# GW-RS485-V40-009.net
KiCad netlist of a schematic drawn in EAGLE
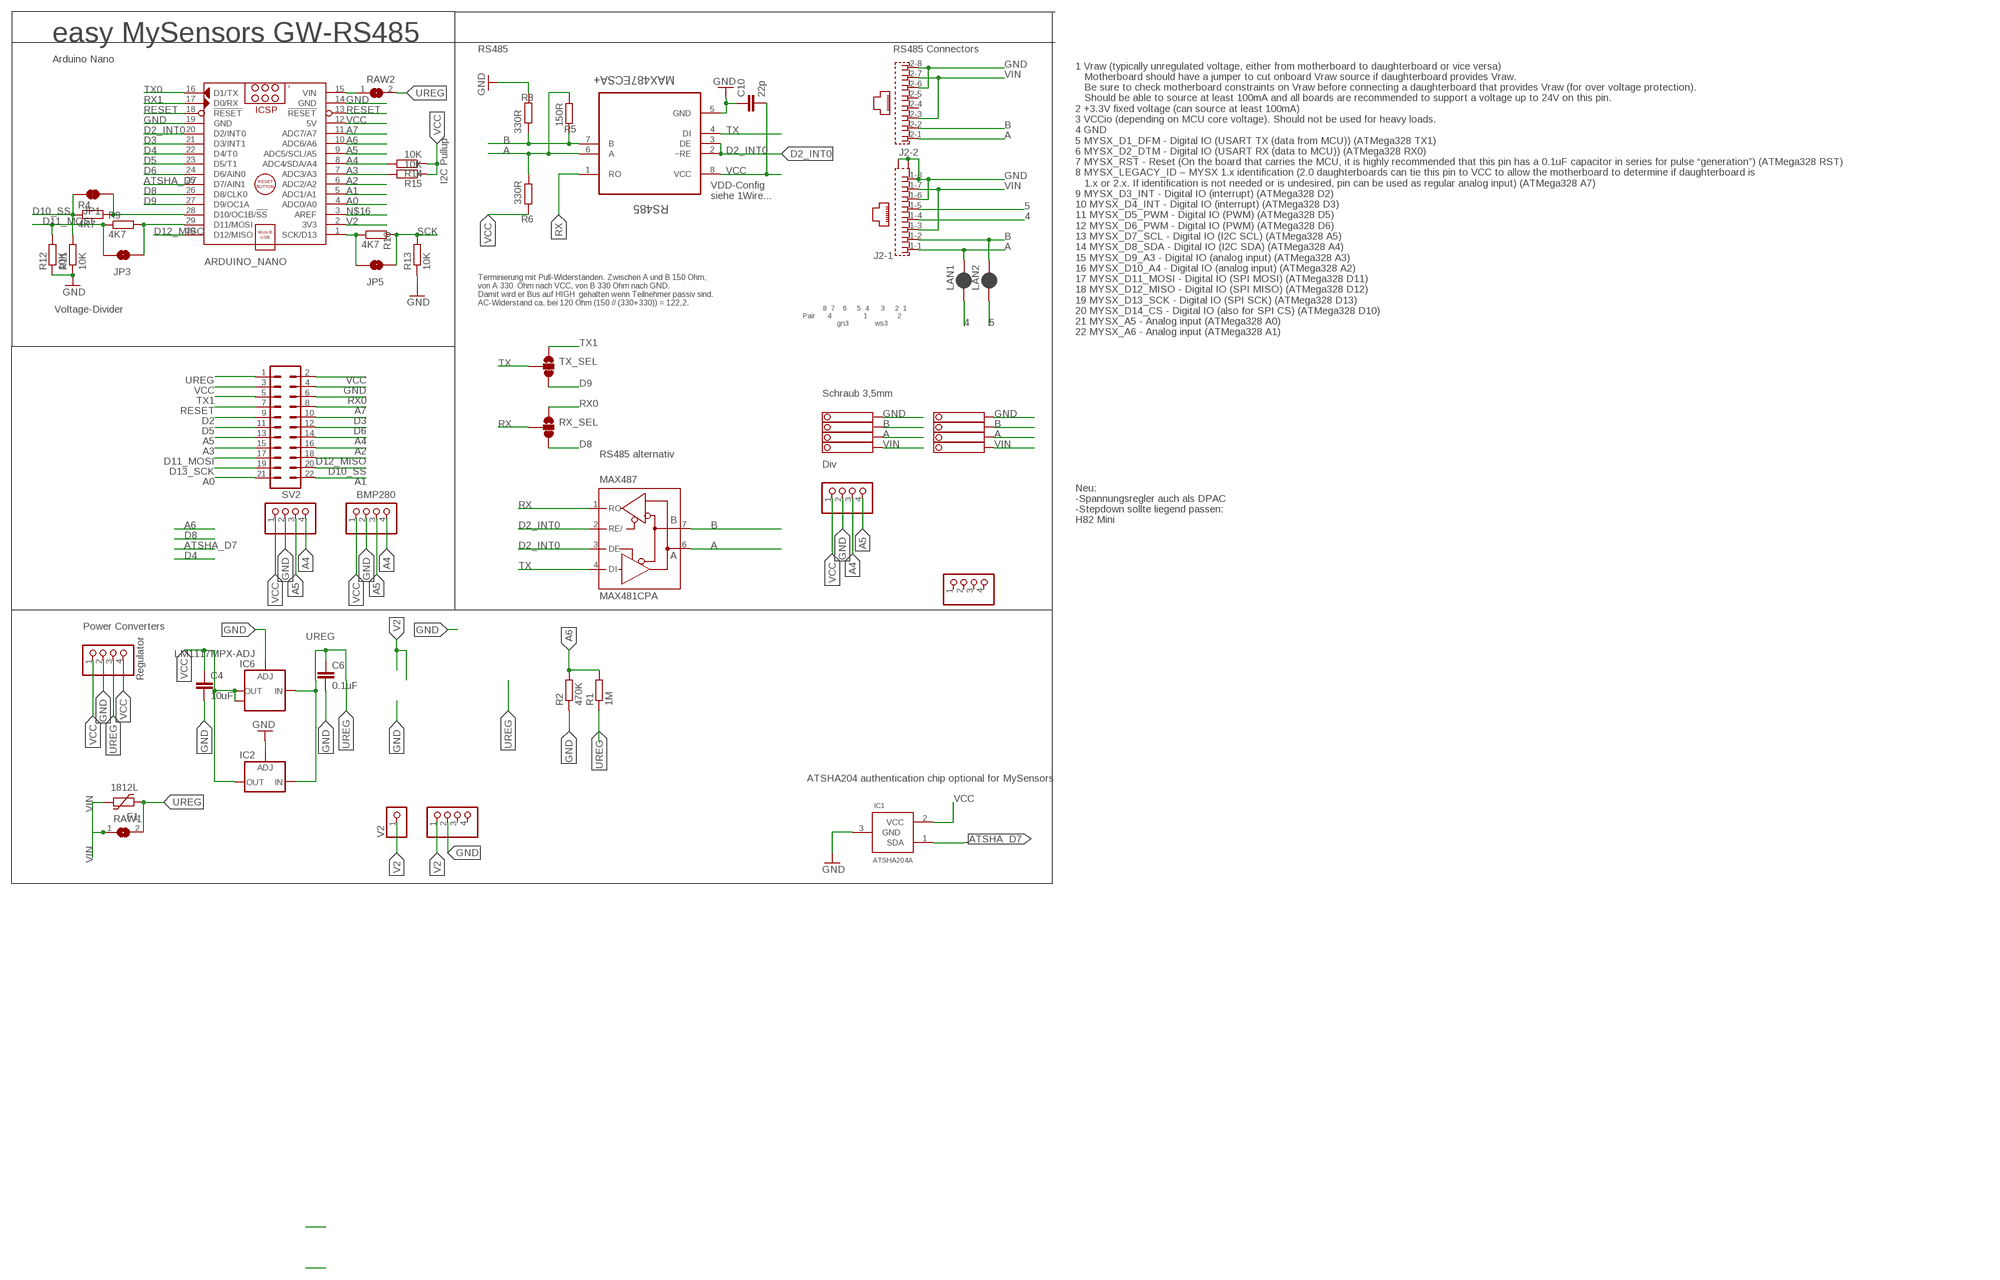
[diagram p0: schematic, sheet 1]

(export (version "E")
  (design (tool "Eeschema 10.0.6"))
  (components
    (comp (ref "ARDUINO_NANO")
      (value "ARDUINO_NANO_OHNE-BOHR")
      (footprint "eagle-import:ARDUINO_NANO")
      (libsource (lib "eagle-import") (part "ARDUINO_NANO_OHNE-BOHR"))
    )
    (comp (ref "BH1750")
      (value "PINHD-1X04_2.54-S")
      (footprint "eagle-import:1X04-S")
      (libsource (lib "eagle-import") (part "PINHD-1X04_2.54-S"))
    )
    (comp (ref "C4")
      (value "10uF")
      (footprint "eagle-import:C1210")
      (libsource (lib "eagle-import") (part "C-EUC1210"))
    )
    (comp (ref "C6")
      (value "0.1uF")
      (footprint "eagle-import:C1206")
      (libsource (lib "eagle-import") (part "C-EUC1206"))
    )
    (comp (ref "C10")
      (value "22p")
      (footprint "eagle-import:C0805")
      (libsource (lib "eagle-import") (part "C-EUC0805"))
    )
    (comp (ref "F1")
      (value "1812L")
      (footprint "eagle-import:1812L")
      (libsource (lib "eagle-import") (part "1812L"))
    )
    (comp (ref "I2C-1")
      (value "PINHD-1X04_2.54-S")
      (footprint "eagle-import:1X04-S")
      (libsource (lib "eagle-import") (part "PINHD-1X04_2.54-S"))
    )
    (comp (ref "I2C-2")
      (value "PINHD-1X04_2.54-S")
      (footprint "eagle-import:1X04-S")
      (libsource (lib "eagle-import") (part "PINHD-1X04_2.54-S"))
    )
    (comp (ref "IC1")
      (value "ATSHA204A")
      (footprint "eagle-import:SOT23")
      (libsource (lib "eagle-import") (part "ATSHA204A"))
    )
    (comp (ref "IC2")
      (value "LD117ADT50TR")
      (footprint "eagle-import:DPACK")
      (libsource (lib "eagle-import") (part "LD117A?DT50TR"))
    )
    (comp (ref "IC6")
      (value "LM1117MPX-ADJ")
      (footprint "eagle-import:SOT223")
      (libsource (lib "eagle-import") (part "LM1117MPX-ADJ"))
    )
    (comp (ref "J2")
      (value "RJ45_2X_NARROW_SHILDPINS_NOCASE")
      (footprint "eagle-import:RJ45_2X_NARROW_SHILDPINS_NOCASE")
      (libsource (lib "eagle-import") (part "RJ45_2X_NARROW_SHILDPINS_NOCASE"))
    )
    (comp (ref "JP1")
      (value "JUMPER-SMT_2_NC_TRACE_SILK")
      (footprint "eagle-import:SMT-JUMPER_2_NC_TRACE_SILK")
      (libsource (lib "eagle-import") (part "JUMPER-SMT_2_NC_TRACE_SILK"))
    )
    (comp (ref "JP2")
      (value "PINHD-1X04_2.54-S")
      (footprint "eagle-import:1X04-S")
      (libsource (lib "eagle-import") (part "PINHD-1X04_2.54-S"))
    )
    (comp (ref "JP3")
      (value "JUMPER-SMT_2_NC_TRACE_SILK")
      (footprint "eagle-import:SMT-JUMPER_2_NC_TRACE_SILK")
      (libsource (lib "eagle-import") (part "JUMPER-SMT_2_NC_TRACE_SILK"))
    )
    (comp (ref "JP5")
      (value "JUMPER-SMT_2_NC_TRACE_SILK")
      (footprint "eagle-import:SMT-JUMPER_2_NC_TRACE_SILK")
      (libsource (lib "eagle-import") (part "JUMPER-SMT_2_NC_TRACE_SILK"))
    )
    (comp (ref "LAN1")
      (value "JUMPER-SMT_2_NC_PASTE_SILK")
      (footprint "eagle-import:SMT-JUMPER_2_NC_PASTE_SILK")
      (libsource (lib "eagle-import") (part "JUMPER-SMT_2_NC_PASTE_SILK"))
    )
    (comp (ref "LAN2")
      (value "JUMPER-SMT_2_NC_PASTE_SILK")
      (footprint "eagle-import:SMT-JUMPER_2_NC_PASTE_SILK")
      (libsource (lib "eagle-import") (part "JUMPER-SMT_2_NC_PASTE_SILK"))
    )
    (comp (ref "MAX487")
      (value "MAX481CPA")
      (footprint "eagle-import:DIL08")
      (libsource (lib "eagle-import") (part "MAX481CPA"))
    )
    (comp (ref "R1")
      (value "1M")
      (footprint "eagle-import:R0805")
      (libsource (lib "eagle-import") (part "R-EU_R0805"))
    )
    (comp (ref "R2")
      (value "470K")
      (footprint "eagle-import:R0805")
      (libsource (lib "eagle-import") (part "R-EU_R0805"))
    )
    (comp (ref "R4")
      (value "4K7")
      (footprint "eagle-import:M0805")
      (libsource (lib "eagle-import") (part "R-EU_M0805"))
    )
    (comp (ref "R5")
      (value "150R")
      (footprint "eagle-import:R0805")
      (libsource (lib "eagle-import") (part "R-EU_R0805"))
    )
    (comp (ref "R6")
      (value "330R")
      (footprint "eagle-import:R0805")
      (libsource (lib "eagle-import") (part "R-EU_R0805"))
    )
    (comp (ref "R8")
      (value "330R")
      (footprint "eagle-import:R0805")
      (libsource (lib "eagle-import") (part "R-EU_R0805"))
    )
    (comp (ref "R9")
      (value "4K7")
      (footprint "eagle-import:M0805")
      (libsource (lib "eagle-import") (part "R-EU_M0805"))
    )
    (comp (ref "R10")
      (value "4K7")
      (footprint "eagle-import:M0805")
      (libsource (lib "eagle-import") (part "R-EU_M0805"))
    )
    (comp (ref "R11")
      (value "10K")
      (footprint "eagle-import:M0805")
      (libsource (lib "eagle-import") (part "R-EU_M0805"))
    )
    (comp (ref "R12")
      (value "10K")
      (footprint "eagle-import:M0805")
      (libsource (lib "eagle-import") (part "R-EU_M0805"))
    )
    (comp (ref "R13")
      (value "10K")
      (footprint "eagle-import:M0805")
      (libsource (lib "eagle-import") (part "R-EU_M0805"))
    )
    (comp (ref "R14")
      (value "10K")
      (footprint "eagle-import:R0805")
      (libsource (lib "eagle-import") (part "R-EU_R0805"))
    )
    (comp (ref "R15")
      (value "10K")
      (footprint "eagle-import:R0805")
      (libsource (lib "eagle-import") (part "R-EU_R0805"))
    )
    (comp (ref "RAW1")
      (value "SJ")
      (footprint "eagle-import:SJ")
      (libsource (lib "eagle-import") (part "SJ"))
    )
    (comp (ref "RAW2")
      (value "SJ")
      (footprint "eagle-import:SJ")
      (libsource (lib "eagle-import") (part "SJ"))
    )
    (comp (ref "RS485")
      (value "MAX487ECSA+")
      (footprint "eagle-import:SOIC127P600X175-8N")
      (libsource (lib "eagle-import") (part "MAX487ECSA+"))
    )
    (comp (ref "RX_SEL")
      (value "JUMPER-SMT_3_1-NC_TRACE_SILK")
      (footprint "eagle-import:SMT-JUMPER_3_1-NC_TRACE_SILK")
      (libsource (lib "eagle-import") (part "JUMPER-SMT_3_1-NC_TRACE_SILK"))
    )
    (comp (ref "STEPDWN")
      (value "PINHD-1X04_2.54-S")
      (footprint "eagle-import:1X04-S")
      (libsource (lib "eagle-import") (part "PINHD-1X04_2.54-S"))
    )
    (comp (ref "SV2")
      (value "MA11-2")
      (footprint "eagle-import:MA11-2")
      (libsource (lib "eagle-import") (part "MA11-2"))
    )
    (comp (ref "TX_SEL")
      (value "JUMPER-SMT_3_1-NC_TRACE_SILK")
      (footprint "eagle-import:SMT-JUMPER_3_1-NC_TRACE_SILK")
      (libsource (lib "eagle-import") (part "JUMPER-SMT_3_1-NC_TRACE_SILK"))
    )
    (comp (ref "V2")
      (value "PINHD-1X1")
      (footprint "eagle-import:1X01")
      (libsource (lib "eagle-import") (part "PINHD-1X1"))
    )
    (comp (ref "V2-")
      (value "PINHD-1X04_2.54-S")
      (footprint "eagle-import:1X04-S")
      (libsource (lib "eagle-import") (part "PINHD-1X04_2.54-S"))
    )
    (comp (ref "X1")
      (value "1751264")
      (footprint "eagle-import:1751264")
      (libsource (lib "eagle-import") (part "1751264"))
    )
    (comp (ref "X4")
      (value "1751264")
      (footprint "eagle-import:1751264")
      (libsource (lib "eagle-import") (part "1751264"))
    )
  )
  (nets
    (net (code "1") (name "/4") (class "Default")
      (node (ref "J2") (pin "1-4") (pinfunction "4_1-4") (pintype "passive"))
      (node (ref "LAN1") (pin "1") (pinfunction "1_1") (pintype "passive"))
    )
    (net (code "2") (name "/5") (class "Default")
      (node (ref "J2") (pin "1-5") (pinfunction "5_1-5") (pintype "passive"))
      (node (ref "LAN2") (pin "1") (pinfunction "1_1") (pintype "passive"))
    )
    (net (code "3") (name "/A") (class "Default")
      (node (ref "J2") (pin "1-1") (pinfunction "1_1-1") (pintype "passive"))
      (node (ref "J2") (pin "2-1") (pinfunction "1_2-1") (pintype "passive"))
      (node (ref "LAN1") (pin "2") (pinfunction "2_2") (pintype "passive"))
      (node (ref "MAX487") (pin "6") (pinfunction "A_6") (pintype "passive"))
      (node (ref "R5") (pin "1") (pinfunction "1_1") (pintype "passive"))
      (node (ref "R6") (pin "2") (pinfunction "2_2") (pintype "passive"))
      (node (ref "RS485") (pin "6") (pinfunction "A_6") (pintype "bidirectional"))
      (node (ref "X1") (pin "2") (pinfunction "K_2") (pintype "passive"))
      (node (ref "X4") (pin "2") (pinfunction "K_2") (pintype "passive"))
    )
    (net (code "4") (name "/A0") (class "Default")
      (node (ref "ARDUINO_NANO") (pin "4") (pinfunction "ADC0/A0_4") (pintype "bidirectional"))
      (node (ref "SV2") (pin "21") (pinfunction "21_21") (pintype "passive"))
    )
    (net (code "5") (name "/A1") (class "Default")
      (node (ref "ARDUINO_NANO") (pin "5") (pinfunction "ADC1/A1_5") (pintype "bidirectional"))
      (node (ref "SV2") (pin "22") (pinfunction "22_22") (pintype "passive"))
    )
    (net (code "6") (name "/A2") (class "Default")
      (node (ref "ARDUINO_NANO") (pin "6") (pinfunction "ADC2/A2_6") (pintype "bidirectional"))
      (node (ref "SV2") (pin "16") (pinfunction "16_16") (pintype "passive"))
    )
    (net (code "7") (name "/A3") (class "Default")
      (node (ref "ARDUINO_NANO") (pin "7") (pinfunction "ADC3/A3_7") (pintype "bidirectional"))
      (node (ref "R15") (pin "2") (pinfunction "2_2") (pintype "passive"))
      (node (ref "SV2") (pin "15") (pinfunction "15_15") (pintype "passive"))
    )
    (net (code "8") (name "/A7") (class "Default")
      (node (ref "ARDUINO_NANO") (pin "11") (pinfunction "ADC7/A7_11") (pintype "bidirectional"))
      (node (ref "SV2") (pin "8") (pinfunction "8_8") (pintype "passive"))
    )
    (net (code "9") (name "/ATSHA_D7") (class "Default")
      (node (ref "ARDUINO_NANO") (pin "25") (pinfunction "D7/AIN1_25") (pintype "bidirectional"))
      (node (ref "IC1") (pin "1") (pinfunction "SDA_1") (pintype "bidirectional"))
    )
    (net (code "10") (name "/B") (class "Default")
      (node (ref "J2") (pin "1-2") (pinfunction "2_1-2") (pintype "passive"))
      (node (ref "J2") (pin "2-2") (pinfunction "2_2-2") (pintype "passive"))
      (node (ref "LAN2") (pin "2") (pinfunction "2_2") (pintype "passive"))
      (node (ref "MAX487") (pin "7") (pinfunction "B_7") (pintype "passive"))
      (node (ref "R5") (pin "2") (pinfunction "2_2") (pintype "passive"))
      (node (ref "R8") (pin "1") (pinfunction "1_1") (pintype "passive"))
      (node (ref "RS485") (pin "7") (pinfunction "B_7") (pintype "bidirectional"))
      (node (ref "X1") (pin "3") (pinfunction "K_3") (pintype "passive"))
      (node (ref "X4") (pin "3") (pinfunction "K_3") (pintype "passive"))
    )
    (net (code "11") (name "/D2") (class "Default")
      (node (ref "SV2") (pin "9") (pinfunction "9_9") (pintype "passive"))
    )
    (net (code "12") (name "/D3") (class "Default")
      (node (ref "ARDUINO_NANO") (pin "21") (pinfunction "D3/INT1_21") (pintype "bidirectional"))
      (node (ref "SV2") (pin "10") (pinfunction "10_10") (pintype "passive"))
    )
    (net (code "13") (name "/D4") (class "Default")
      (node (ref "ARDUINO_NANO") (pin "22") (pinfunction "D4/T0_22") (pintype "bidirectional"))
    )
    (net (code "14") (name "/D5") (class "Default")
      (node (ref "ARDUINO_NANO") (pin "23") (pinfunction "D5/T1_23") (pintype "bidirectional"))
      (node (ref "SV2") (pin "11") (pinfunction "11_11") (pintype "passive"))
    )
    (net (code "15") (name "/D6") (class "Default")
      (node (ref "ARDUINO_NANO") (pin "24") (pinfunction "D6/AIN0_24") (pintype "bidirectional"))
      (node (ref "SV2") (pin "12") (pinfunction "12_12") (pintype "passive"))
    )
    (net (code "16") (name "/D8") (class "Default")
      (node (ref "ARDUINO_NANO") (pin "26") (pinfunction "D8/CLK0_26") (pintype "bidirectional"))
      (node (ref "RX_SEL") (pin "3") (pinfunction "3_3") (pintype "passive"))
    )
    (net (code "17") (name "/D9") (class "Default")
      (node (ref "ARDUINO_NANO") (pin "27") (pinfunction "D9/OC1A_27") (pintype "bidirectional"))
      (node (ref "TX_SEL") (pin "3") (pinfunction "3_3") (pintype "passive"))
    )
    (net (code "18") (name "/D10_SS") (class "Default")
      (node (ref "JP1") (pin "1") (pinfunction "1_1") (pintype "passive"))
      (node (ref "R11") (pin "2") (pinfunction "2_2") (pintype "passive"))
      (node (ref "R4") (pin "1") (pinfunction "1_1") (pintype "passive"))
      (node (ref "SV2") (pin "20") (pinfunction "20_20") (pintype "passive"))
    )
    (net (code "19") (name "/D11_MOSI") (class "Default")
      (node (ref "JP3") (pin "1") (pinfunction "1_1") (pintype "passive"))
      (node (ref "R12") (pin "2") (pinfunction "2_2") (pintype "passive"))
      (node (ref "R9") (pin "1") (pinfunction "1_1") (pintype "passive"))
      (node (ref "SV2") (pin "17") (pinfunction "17_17") (pintype "passive"))
    )
    (net (code "20") (name "/D12_MISO") (class "Default")
      (node (ref "ARDUINO_NANO") (pin "30") (pinfunction "D12/MISO_30") (pintype "bidirectional"))
      (node (ref "SV2") (pin "18") (pinfunction "18_18") (pintype "passive"))
    )
    (net (code "21") (name "/D13_SCK") (class "Default")
      (node (ref "SV2") (pin "19") (pinfunction "19_19") (pintype "passive"))
    )
    (net (code "22") (name "/N$16") (class "Default")
      (node (ref "ARDUINO_NANO") (pin "3") (pinfunction "AREF_3") (pintype "input"))
    )
    (net (code "23") (name "/RESET") (class "Default")
      (node (ref "ARDUINO_NANO") (pin "13") (pinfunction "~{RESET}_13") (pintype "input"))
      (node (ref "ARDUINO_NANO") (pin "18") (pinfunction "~{RESET}_18") (pintype "input"))
      (node (ref "SV2") (pin "7") (pinfunction "7_7") (pintype "passive"))
    )
    (net (code "24") (name "/RX0") (class "Default")
      (node (ref "RX_SEL") (pin "1") (pinfunction "1_1") (pintype "passive"))
      (node (ref "SV2") (pin "6") (pinfunction "6_6") (pintype "passive"))
    )
    (net (code "25") (name "/RX1") (class "Default")
      (node (ref "ARDUINO_NANO") (pin "17") (pinfunction "D0/RX_17") (pintype "bidirectional"))
    )
    (net (code "26") (name "/SCK") (class "Default")
      (node (ref "JP5") (pin "2") (pinfunction "2_2") (pintype "passive"))
      (node (ref "R10") (pin "2") (pinfunction "2_2") (pintype "passive"))
      (node (ref "R13") (pin "2") (pinfunction "2_2") (pintype "passive"))
    )
    (net (code "27") (name "/TX") (class "Default")
      (node (ref "MAX487") (pin "4") (pinfunction "DI_4") (pintype "input"))
      (node (ref "RS485") (pin "4") (pinfunction "DI_4") (pintype "input"))
      (node (ref "TX_SEL") (pin "2") (pinfunction "2_2") (pintype "passive"))
    )
    (net (code "28") (name "/TX0") (class "Default")
      (node (ref "ARDUINO_NANO") (pin "16") (pinfunction "D1/TX_16") (pintype "bidirectional"))
    )
    (net (code "29") (name "/TX1") (class "Default")
      (node (ref "SV2") (pin "5") (pinfunction "5_5") (pintype "passive"))
      (node (ref "TX_SEL") (pin "1") (pinfunction "1_1") (pintype "passive"))
    )
    (net (code "30") (name "/VIN") (class "Default")
      (node (ref "F1") (pin "P$2") (pinfunction "2_P$2") (pintype "passive"))
      (node (ref "J2") (pin "1-3") (pinfunction "3_1-3") (pintype "passive"))
      (node (ref "J2") (pin "1-7") (pinfunction "7_1-7") (pintype "passive"))
      (node (ref "J2") (pin "2-3") (pinfunction "3_2-3") (pintype "passive"))
      (node (ref "J2") (pin "2-7") (pinfunction "7_2-7") (pintype "passive"))
      (node (ref "RAW1") (pin "1") (pinfunction "1_1") (pintype "passive"))
      (node (ref "X1") (pin "1") (pinfunction "K_1") (pintype "passive"))
      (node (ref "X4") (pin "1") (pinfunction "K_1") (pintype "passive"))
    )
    (net (code "31") (name "A4") (class "Default")
      (node (ref "ARDUINO_NANO") (pin "8") (pinfunction "ADC4/SDA/A4_8") (pintype "bidirectional"))
      (node (ref "BH1750") (pin "4") (pinfunction "4_4") (pintype "passive"))
      (node (ref "I2C-1") (pin "4") (pinfunction "4_4") (pintype "passive"))
      (node (ref "I2C-2") (pin "3") (pinfunction "3_3") (pintype "passive"))
      (node (ref "R14") (pin "2") (pinfunction "2_2") (pintype "passive"))
      (node (ref "SV2") (pin "14") (pinfunction "14_14") (pintype "passive"))
    )
    (net (code "32") (name "A5") (class "Default")
      (node (ref "ARDUINO_NANO") (pin "9") (pinfunction "ADC5/SCL/A5_9") (pintype "bidirectional"))
      (node (ref "BH1750") (pin "3") (pinfunction "3_3") (pintype "passive"))
      (node (ref "I2C-1") (pin "3") (pinfunction "3_3") (pintype "passive"))
      (node (ref "I2C-2") (pin "4") (pinfunction "4_4") (pintype "passive"))
      (node (ref "SV2") (pin "13") (pinfunction "13_13") (pintype "passive"))
    )
    (net (code "33") (name "A6") (class "Default")
      (node (ref "ARDUINO_NANO") (pin "10") (pinfunction "ADC6/A6_10") (pintype "bidirectional"))
      (node (ref "R1") (pin "2") (pinfunction "2_2") (pintype "passive"))
      (node (ref "R2") (pin "2") (pinfunction "2_2") (pintype "passive"))
    )
    (net (code "34") (name "D2_INT0") (class "Default")
      (node (ref "ARDUINO_NANO") (pin "20") (pinfunction "D2/INT0_20") (pintype "bidirectional"))
      (node (ref "MAX487") (pin "2") (pinfunction "RE/_2") (pintype "input"))
      (node (ref "MAX487") (pin "3") (pinfunction "DE_3") (pintype "input"))
      (node (ref "RS485") (pin "2") (pinfunction "~{RE}_2") (pintype "input"))
      (node (ref "RS485") (pin "3") (pinfunction "DE_3") (pintype "input"))
    )
    (net (code "35") (name "GND") (class "Default")
      (node (ref "ARDUINO_NANO") (pin "14") (pinfunction "GND_14") (pintype "power_in"))
      (node (ref "ARDUINO_NANO") (pin "19") (pinfunction "GND_19") (pintype "power_in"))
      (node (ref "BH1750") (pin "2") (pinfunction "2_2") (pintype "passive"))
      (node (ref "C10") (pin "1") (pinfunction "1_1") (pintype "passive"))
      (node (ref "C4") (pin "2") (pinfunction "2_2") (pintype "passive"))
      (node (ref "C6") (pin "2") (pinfunction "2_2") (pintype "passive"))
      (node (ref "I2C-1") (pin "2") (pinfunction "2_2") (pintype "passive"))
      (node (ref "I2C-2") (pin "2") (pinfunction "2_2") (pintype "passive"))
      (node (ref "IC1") (pin "3") (pinfunction "GND_3") (pintype "bidirectional"))
      (node (ref "IC2") (pin "1") (pinfunction "ADJ_1") (pintype "input"))
      (node (ref "IC6") (pin "1") (pinfunction "ADJ_1") (pintype "input"))
      (node (ref "J2") (pin "1-6") (pinfunction "6_1-6") (pintype "passive"))
      (node (ref "J2") (pin "1-8") (pinfunction "8_1-8") (pintype "passive"))
      (node (ref "J2") (pin "2-6") (pinfunction "6_2-6") (pintype "passive"))
      (node (ref "J2") (pin "2-8") (pinfunction "8_2-8") (pintype "passive"))
      (node (ref "J2") (pin "G1") (pinfunction "S1_G1") (pintype "passive"))
      (node (ref "J2") (pin "G3") (pinfunction "S2_G3") (pintype "passive"))
      (node (ref "R11") (pin "1") (pinfunction "1_1") (pintype "passive"))
      (node (ref "R12") (pin "1") (pinfunction "1_1") (pintype "passive"))
      (node (ref "R13") (pin "1") (pinfunction "1_1") (pintype "passive"))
      (node (ref "R2") (pin "1") (pinfunction "1_1") (pintype "passive"))
      (node (ref "R8") (pin "2") (pinfunction "2_2") (pintype "passive"))
      (node (ref "RS485") (pin "5") (pinfunction "GND_5") (pintype "passive"))
      (node (ref "STEPDWN") (pin "2") (pinfunction "2_2") (pintype "passive"))
      (node (ref "SV2") (pin "4") (pinfunction "4_4") (pintype "passive"))
      (node (ref "V2-") (pin "2") (pinfunction "2_2") (pintype "passive"))
      (node (ref "X1") (pin "4") (pinfunction "K_4") (pintype "passive"))
      (node (ref "X4") (pin "4") (pinfunction "K_4") (pintype "passive"))
    )
    (net (code "36") (name "Net-(ARDUINO_NANO-D10{slash}OC1B{slash}~{SS})") (class "Default")
      (node (ref "ARDUINO_NANO") (pin "28") (pinfunction "D10/OC1B/~{SS}_28") (pintype "bidirectional"))
      (node (ref "JP1") (pin "2") (pinfunction "2_2") (pintype "passive"))
      (node (ref "R4") (pin "2") (pinfunction "2_2") (pintype "passive"))
    )
    (net (code "37") (name "Net-(ARDUINO_NANO-D11{slash}MOSI)") (class "Default")
      (node (ref "ARDUINO_NANO") (pin "29") (pinfunction "D11/MOSI_29") (pintype "bidirectional"))
      (node (ref "JP3") (pin "2") (pinfunction "2_2") (pintype "passive"))
      (node (ref "R9") (pin "2") (pinfunction "2_2") (pintype "passive"))
    )
    (net (code "38") (name "Net-(ARDUINO_NANO-SCK{slash}D13)") (class "Default")
      (node (ref "ARDUINO_NANO") (pin "1") (pinfunction "SCK/D13_1") (pintype "bidirectional"))
      (node (ref "JP5") (pin "1") (pinfunction "1_1") (pintype "passive"))
      (node (ref "R10") (pin "1") (pinfunction "1_1") (pintype "passive"))
    )
    (net (code "39") (name "Net-(ARDUINO_NANO-VIN)") (class "Default")
      (node (ref "ARDUINO_NANO") (pin "15") (pinfunction "VIN_15") (pintype "power_in"))
      (node (ref "RAW2") (pin "1") (pinfunction "1_1") (pintype "passive"))
    )
    (net (code "40") (name "RX") (class "Default")
      (node (ref "MAX487") (pin "1") (pinfunction "RO_1") (pintype "output"))
      (node (ref "RS485") (pin "1") (pinfunction "RO_1") (pintype "output"))
      (node (ref "RX_SEL") (pin "2") (pinfunction "2_2") (pintype "passive"))
    )
    (net (code "41") (name "UREG") (class "Default")
      (node (ref "C6") (pin "1") (pinfunction "1_1") (pintype "passive"))
      (node (ref "F1") (pin "P$1") (pinfunction "1_P$1") (pintype "passive"))
      (node (ref "IC2") (pin "3") (pinfunction "IN_3") (pintype "input"))
      (node (ref "IC6") (pin "3") (pinfunction "IN_3") (pintype "input"))
      (node (ref "R1") (pin "1") (pinfunction "1_1") (pintype "passive"))
      (node (ref "RAW1") (pin "2") (pinfunction "2_2") (pintype "passive"))
      (node (ref "RAW2") (pin "2") (pinfunction "2_2") (pintype "passive"))
      (node (ref "STEPDWN") (pin "3") (pinfunction "3_3") (pintype "passive"))
      (node (ref "SV2") (pin "1") (pinfunction "1_1") (pintype "passive"))
    )
    (net (code "42") (name "V2") (class "Default")
      (node (ref "ARDUINO_NANO") (pin "2") (pinfunction "3V3_2") (pintype "output"))
      (node (ref "V2") (pin "1") (pinfunction "1_1") (pintype "passive"))
      (node (ref "V2-") (pin "1") (pinfunction "1_1") (pintype "passive"))
    )
    (net (code "43") (name "VCC") (class "Default")
      (node (ref "ARDUINO_NANO") (pin "12") (pinfunction "5V_12") (pintype "power_in"))
      (node (ref "BH1750") (pin "1") (pinfunction "1_1") (pintype "passive"))
      (node (ref "C10") (pin "2") (pinfunction "2_2") (pintype "passive"))
      (node (ref "C4") (pin "1") (pinfunction "1_1") (pintype "passive"))
      (node (ref "I2C-1") (pin "1") (pinfunction "1_1") (pintype "passive"))
      (node (ref "I2C-2") (pin "1") (pinfunction "1_1") (pintype "passive"))
      (node (ref "IC1") (pin "2") (pinfunction "VCC_2") (pintype "bidirectional"))
      (node (ref "IC2") (pin "4") (pinfunction "OUT_4") (pintype "passive"))
      (node (ref "IC6") (pin "2") (pinfunction "OUT_2") (pintype "passive"))
      (node (ref "IC6") (pin "TAB") (pinfunction "OUT1_TAB") (pintype "passive"))
      (node (ref "R14") (pin "1") (pinfunction "1_1") (pintype "passive"))
      (node (ref "R15") (pin "1") (pinfunction "1_1") (pintype "passive"))
      (node (ref "R6") (pin "1") (pinfunction "1_1") (pintype "passive"))
      (node (ref "RS485") (pin "8") (pinfunction "VCC_8") (pintype "power_in"))
      (node (ref "STEPDWN") (pin "1") (pinfunction "1_1") (pintype "passive"))
      (node (ref "STEPDWN") (pin "4") (pinfunction "4_4") (pintype "passive"))
      (node (ref "SV2") (pin "2") (pinfunction "2_2") (pintype "passive"))
      (node (ref "SV2") (pin "3") (pinfunction "3_3") (pintype "passive"))
    )
    (net (code "44") (name "unconnected-(J2B-4-Pad2-4)") (class "Default")
      (node (ref "J2") (pin "2-4") (pinfunction "4_2-4") (pintype "passive"))
    )
    (net (code "45") (name "unconnected-(J2B-5-Pad2-5)") (class "Default")
      (node (ref "J2") (pin "2-5") (pinfunction "5_2-5") (pintype "passive"))
    )
    (net (code "46") (name "unconnected-(JP2-Pad1)") (class "Default")
      (node (ref "JP2") (pin "1") (pinfunction "1_1") (pintype "passive"))
    )
    (net (code "47") (name "unconnected-(JP2-Pad2)") (class "Default")
      (node (ref "JP2") (pin "2") (pinfunction "2_2") (pintype "passive"))
    )
    (net (code "48") (name "unconnected-(JP2-Pad3)") (class "Default")
      (node (ref "JP2") (pin "3") (pinfunction "3_3") (pintype "passive"))
    )
    (net (code "49") (name "unconnected-(JP2-Pad4)") (class "Default")
      (node (ref "JP2") (pin "4") (pinfunction "4_4") (pintype "passive"))
    )
    (net (code "50") (name "unconnected-(V2--Pad3)") (class "Default")
      (node (ref "V2-") (pin "3") (pinfunction "3_3") (pintype "passive"))
    )
    (net (code "51") (name "unconnected-(V2--Pad4)") (class "Default")
      (node (ref "V2-") (pin "4") (pinfunction "4_4") (pintype "passive"))
    )
  )
)
